# 3_Phase_Amp.net
KiCad netlist of a schematic drawn in Altium Designer
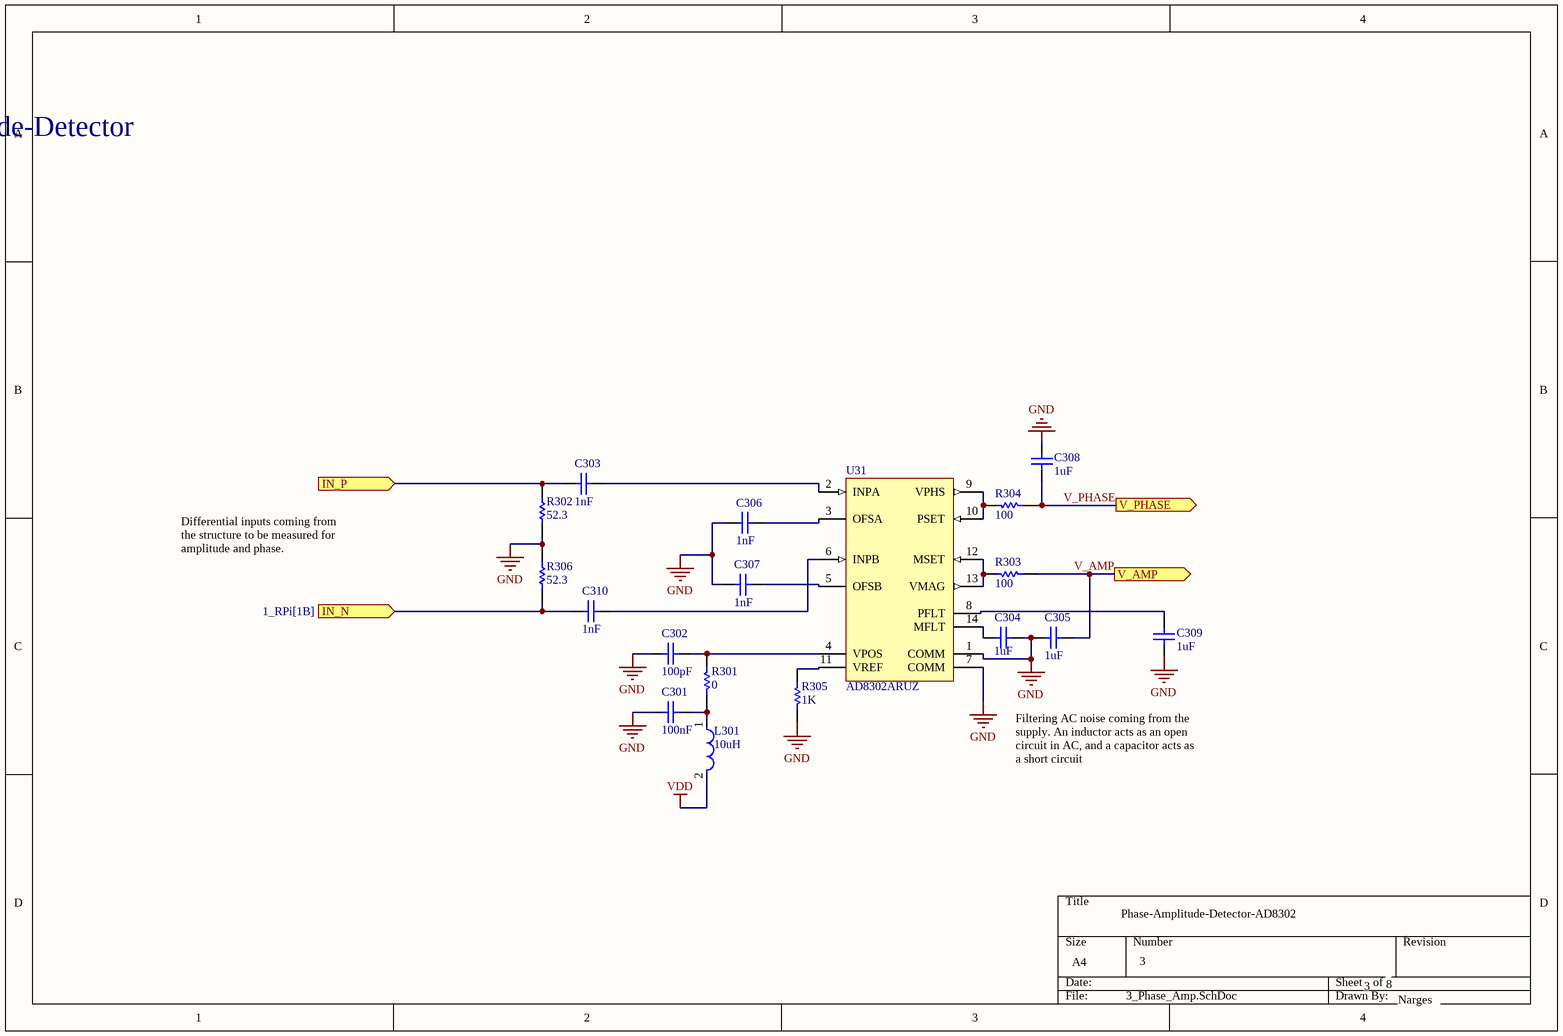
[diagram p0: 3_Phase_Amp.SchDoc]

(export (version "E")
  (design (tool "Eeschema 10.0.6"))
  (components
    (comp (ref "C301")
      (value "100nF")
      (footprint "CAPC1005X55X30LL05T10")
      (description "generic")
      (libsource (lib "RPI_EIT_SchLib") (part "Capacitor"))
    )
    (comp (ref "C302")
      (value "100pF")
      (footprint "CAPC1005X55X30LL05T10")
      (description "generic")
      (libsource (lib "RPI_EIT_SchLib") (part "Capacitor"))
    )
    (comp (ref "C303")
      (value "1nF")
      (footprint "CAPC1005X55X30LL05T10")
      (description "generic")
      (libsource (lib "RPI_EIT_SchLib") (part "Capacitor"))
    )
    (comp (ref "C304")
      (value "1uF")
      (footprint "CAPC1005X55X30LL05T10")
      (description "generic")
      (libsource (lib "RPI_EIT_SchLib") (part "Capacitor"))
    )
    (comp (ref "C305")
      (value "1uF")
      (footprint "CAPC1005X55X30LL05T10")
      (description "generic")
      (libsource (lib "RPI_EIT_SchLib") (part "Capacitor"))
    )
    (comp (ref "C306")
      (value "1nF")
      (footprint "CAPC1005X55X30LL05T10")
      (description "generic")
      (libsource (lib "RPI_EIT_SchLib") (part "Capacitor"))
    )
    (comp (ref "C307")
      (value "1nF")
      (footprint "CAPC1005X55X30LL05T10")
      (description "generic")
      (libsource (lib "RPI_EIT_SchLib") (part "Capacitor"))
    )
    (comp (ref "C308")
      (value "1uF")
      (footprint "CAPC1005X55X30LL05T10")
      (description "generic")
      (libsource (lib "RPI_EIT_SchLib") (part "Capacitor"))
    )
    (comp (ref "C309")
      (value "1uF")
      (footprint "CAPC1005X55X30LL05T10")
      (description "generic")
      (libsource (lib "RPI_EIT_SchLib") (part "Capacitor"))
    )
    (comp (ref "C310")
      (value "1nF")
      (footprint "CAPC1005X55X30LL05T10")
      (description "generic")
      (libsource (lib "RPI_EIT_SchLib") (part "Capacitor"))
    )
    (comp (ref "L301")
      (value "LQW18AN10NG00D")
      (footprint "IND_0402HL-821XJRU")
      (description "Wire Wound RF Inductor 10nH ±2% 650mA 0.11Ω 0603 (1608)")
      (fields (field (name "INDUCTANCE") "10uH") (field (name "TOLERANCE") "2%"))
      (libsource (lib "RPI_EIT_SchLib") (part "725321dda6339637d4d059423bc1c3c"))
    )
    (comp (ref "R301")
      (value "0")
      (footprint "RESC1005X40X25LL10T10")
      (description "generic")
      (fields (field (name "PART NUMBER") "RC0402FR-0747KL") (field (name "MANUFACTURER") "Yageo / Phycomp"))
      (libsource (lib "RPI_EIT_SchLib") (part "Resistor"))
    )
    (comp (ref "R302")
      (value "52.3")
      (footprint "RESC1005X40X25LL10T10")
      (description "generic")
      (fields (field (name "PART NUMBER") "RC0402FR-0747KL") (field (name "MANUFACTURER") "Yageo / Phycomp"))
      (libsource (lib "RPI_EIT_SchLib") (part "Resistor"))
    )
    (comp (ref "R303")
      (value "100")
      (footprint "RESC1005X40X25LL10T10")
      (description "generic")
      (fields (field (name "PART NUMBER") "RC0402FR-0747KL") (field (name "MANUFACTURER") "Yageo / Phycomp"))
      (libsource (lib "RPI_EIT_SchLib") (part "Resistor"))
    )
    (comp (ref "R304")
      (value "100")
      (footprint "RESC1005X40X25LL10T10")
      (description "generic")
      (fields (field (name "PART NUMBER") "RC0402FR-0747KL") (field (name "MANUFACTURER") "Yageo / Phycomp"))
      (libsource (lib "RPI_EIT_SchLib") (part "Resistor"))
    )
    (comp (ref "R305")
      (value "1K")
      (footprint "RESC1005X40X25LL10T10")
      (description "generic")
      (fields (field (name "PART NUMBER") "RC0402FR-0747KL") (field (name "MANUFACTURER") "Yageo / Phycomp"))
      (libsource (lib "RPI_EIT_SchLib") (part "Resistor"))
    )
    (comp (ref "R306")
      (value "52.3")
      (footprint "RESC1005X40X25LL10T10")
      (description "generic")
      (fields (field (name "PART NUMBER") "RC0402FR-0747KL") (field (name "MANUFACTURER") "Yageo / Phycomp"))
      (libsource (lib "RPI_EIT_SchLib") (part "Resistor"))
    )
    (comp (ref "U31")
      (value "AD8302ARUZ")
      (footprint "ADI-RU-14_L")
      (description "LF-2.7 GHz RF/IF Gain and Phase Detector, 60ns Response Time, RU-14, Pb-Free, 96 Tube")
      (libsource (lib "Altium Content Vault") (part "ADI-AD8302-RU-14"))
    )
  )
  (nets
    (net (code "1") (name "/IN_N") (class "Default")
      (node (ref "C310") (pin "2") (pinfunction "2_2") (pintype "passive"))
      (node (ref "R306") (pin "1") (pinfunction "1_1") (pintype "passive"))
    )
    (net (code "2") (name "/IN_P") (class "Default")
      (node (ref "C303") (pin "1") (pinfunction "1_1") (pintype "passive"))
      (node (ref "R302") (pin "2") (pinfunction "2_2") (pintype "passive"))
    )
    (net (code "3") (name "/V_AMP") (class "Default")
      (node (ref "C305") (pin "2") (pinfunction "2_2") (pintype "passive"))
      (node (ref "R303") (pin "2") (pinfunction "2_2") (pintype "passive"))
    )
    (net (code "4") (name "/V_PHASE") (class "Default")
      (node (ref "C308") (pin "2") (pinfunction "2_2") (pintype "passive"))
      (node (ref "R304") (pin "2") (pinfunction "2_2") (pintype "passive"))
    )
    (net (code "5") (name "GND") (class "Default")
      (node (ref "C301") (pin "1") (pinfunction "1_1") (pintype "passive"))
      (node (ref "C302") (pin "1") (pinfunction "1_1") (pintype "passive"))
      (node (ref "C304") (pin "1") (pinfunction "1_1") (pintype "passive"))
      (node (ref "C305") (pin "1") (pinfunction "1_1") (pintype "passive"))
      (node (ref "C306") (pin "2") (pinfunction "2_2") (pintype "passive"))
      (node (ref "C307") (pin "2") (pinfunction "2_2") (pintype "passive"))
      (node (ref "C308") (pin "1") (pinfunction "1_1") (pintype "passive"))
      (node (ref "C309") (pin "1") (pinfunction "1_1") (pintype "passive"))
      (node (ref "R302") (pin "1") (pinfunction "1_1") (pintype "passive"))
      (node (ref "R305") (pin "1") (pinfunction "1_1") (pintype "passive"))
      (node (ref "R306") (pin "2") (pinfunction "2_2") (pintype "passive"))
      (node (ref "U31") (pin "1") (pinfunction "COMM_1") (pintype "power_in"))
      (node (ref "U31") (pin "7") (pinfunction "COMM_7") (pintype "power_in"))
    )
    (net (code "6") (name "Net-(C301-Pad2)") (class "Default")
      (node (ref "C301") (pin "2") (pinfunction "2_2") (pintype "passive"))
      (node (ref "L301") (pin "1") (pinfunction "1_1") (pintype "passive"))
      (node (ref "R301") (pin "2") (pinfunction "2_2") (pintype "passive"))
    )
    (net (code "7") (name "Net-(U31-INPA)") (class "Default")
      (node (ref "C303") (pin "2") (pinfunction "2_2") (pintype "passive"))
      (node (ref "U31") (pin "2") (pinfunction "INPA_2") (pintype "input"))
    )
    (net (code "8") (name "Net-(U31-INPB)") (class "Default")
      (node (ref "C310") (pin "1") (pinfunction "1_1") (pintype "passive"))
      (node (ref "U31") (pin "6") (pinfunction "INPB_6") (pintype "input"))
    )
    (net (code "9") (name "Net-(U31-MFLT)") (class "Default")
      (node (ref "C304") (pin "2") (pinfunction "2_2") (pintype "passive"))
      (node (ref "U31") (pin "14") (pinfunction "MFLT_14") (pintype "passive"))
    )
    (net (code "10") (name "Net-(U31-MSET)") (class "Default")
      (node (ref "R303") (pin "1") (pinfunction "1_1") (pintype "passive"))
      (node (ref "U31") (pin "12") (pinfunction "MSET_12") (pintype "input"))
      (node (ref "U31") (pin "13") (pinfunction "VMAG_13") (pintype "output"))
    )
    (net (code "11") (name "Net-(U31-OFSA)") (class "Default")
      (node (ref "C306") (pin "1") (pinfunction "1_1") (pintype "passive"))
      (node (ref "U31") (pin "3") (pinfunction "OFSA_3") (pintype "passive"))
    )
    (net (code "12") (name "Net-(U31-OFSB)") (class "Default")
      (node (ref "C307") (pin "1") (pinfunction "1_1") (pintype "passive"))
      (node (ref "U31") (pin "5") (pinfunction "OFSB_5") (pintype "passive"))
    )
    (net (code "13") (name "Net-(U31-PFLT)") (class "Default")
      (node (ref "C309") (pin "2") (pinfunction "2_2") (pintype "passive"))
      (node (ref "U31") (pin "8") (pinfunction "PFLT_8") (pintype "passive"))
    )
    (net (code "14") (name "Net-(U31-PSET)") (class "Default")
      (node (ref "R304") (pin "1") (pinfunction "1_1") (pintype "passive"))
      (node (ref "U31") (pin "10") (pinfunction "PSET_10") (pintype "input"))
      (node (ref "U31") (pin "9") (pinfunction "VPHS_9") (pintype "output"))
    )
    (net (code "15") (name "Net-(U31-VPOS)") (class "Default")
      (node (ref "C302") (pin "2") (pinfunction "2_2") (pintype "passive"))
      (node (ref "R301") (pin "1") (pinfunction "1_1") (pintype "passive"))
      (node (ref "U31") (pin "4") (pinfunction "VPOS_4") (pintype "power_in"))
    )
    (net (code "16") (name "Net-(U31-VREF)") (class "Default")
      (node (ref "R305") (pin "2") (pinfunction "2_2") (pintype "passive"))
      (node (ref "U31") (pin "11") (pinfunction "VREF_11") (pintype "power_in"))
    )
    (net (code "17") (name "VDD") (class "Default")
      (node (ref "L301") (pin "2") (pinfunction "2_2") (pintype "passive"))
    )
  )
)
